# 6_-OPI_POWER.net
KiCad netlist of a schematic drawn in Altium Designer
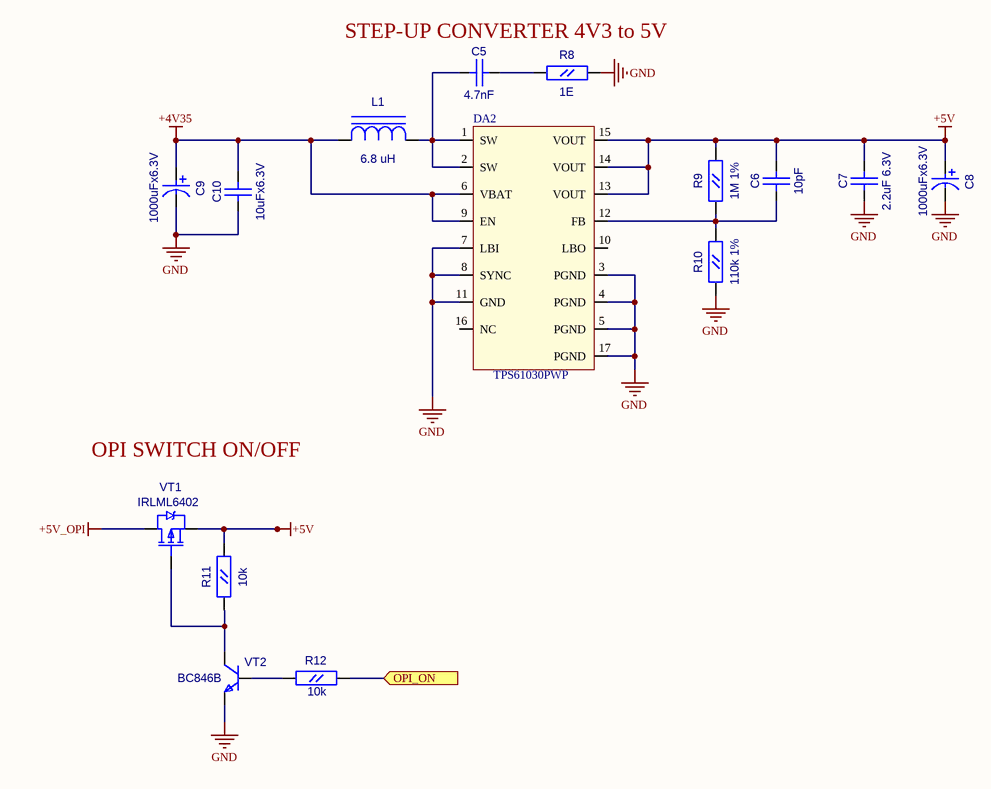
[diagram p0: [6]-OPI_POWER.SchDoc]

(export (version "E")
  (design (tool "Eeschema 10.0.6"))
  (components
    (comp (ref "C5")
      (value "4.7nF")
      (footprint "CC0603")
      (description "CC0603")
      (libsource (lib "gprs_modem_2") (part "CC0603"))
    )
    (comp (ref "C6")
      (value "10pF")
      (footprint "CC0603")
      (description "CC0603")
      (libsource (lib "gprs_modem_2") (part "CC0603"))
    )
    (comp (ref "C7")
      (value "2.2uF 6.3V")
      (footprint "CC0805")
      (description "CC0805")
      (libsource (lib "gprs_modem_2") (part "CC0805"))
    )
    (comp (ref "C8")
      (value "1000uFx6.3V")
      (footprint "CC8X3.5")
      (description "CAP0.35")
      (libsource (lib "gprs_modem_2") (part "CAP0.35"))
    )
    (comp (ref "C9")
      (value "1000uFx6.3V")
      (footprint "CC8X3.5")
      (description "CAP0.35")
      (libsource (lib "gprs_modem_2") (part "CAP0.35"))
    )
    (comp (ref "C10")
      (value "10uFx6.3V")
      (footprint "CC0805")
      (description "CC0805")
      (libsource (lib "gprs_modem_2") (part "CC0805"))
    )
    (comp (ref "DA2")
      (value "TPS61030PWP")
      (footprint "R-PDSO-G16")
      (description "Boost converter")
      (libsource (lib "gprs_modem") (part "TPS61030PWP"))
    )
    (comp (ref "L1")
      (value "6.8 uH")
      (footprint "SDR0805")
      (description "SDR0805")
      (libsource (lib "gprs_modem_2") (part "SDR0805"))
    )
    (comp (ref "R8")
      (value "1E")
      (footprint "RC0603")
      (description "RC0603")
      (libsource (lib "gprs_modem_2") (part "RC0603"))
    )
    (comp (ref "R9")
      (value "1M 1%")
      (footprint "RC0603")
      (description "RC0603")
      (libsource (lib "gprs_modem_2") (part "RC0603"))
    )
    (comp (ref "R10")
      (value "110k 1%")
      (footprint "RC0603")
      (description "RC0603")
      (libsource (lib "gprs_modem_2") (part "RC0603"))
    )
    (comp (ref "R11")
      (value "10k")
      (footprint "RC0603")
      (description "RC0603")
      (libsource (lib "gprs_modem_2") (part "RC0603"))
    )
    (comp (ref "R12")
      (value "10k")
      (footprint "RC0603")
      (description "RC0603")
      (libsource (lib "fizik_lib") (part "RC0603"))
    )
    (comp (ref "VT1")
      (value "IRLML6402")
      (footprint "SOT-23(123)")
      (description "HEXFET Power MOSFET")
      (libsource (lib "gprs_modem_2") (part "IRLML6402"))
    )
    (comp (ref "VT2")
      (value "BC846B")
      (footprint "SOT-23(123)")
      (description "BC846BLT1")
      (libsource (lib "gprs_modem_2") (part "BC846BLT1"))
    )
  )
  (nets
    (net (code "1") (name "+4V35") (class "Default")
      (node (ref "C10") (pin "2") (pinfunction "B_2") (pintype "passive"))
      (node (ref "C9") (pin "1") (pintype "passive"))
      (node (ref "DA2") (pin "6") (pinfunction "VBAT_6") (pintype "passive"))
      (node (ref "DA2") (pin "9") (pinfunction "EN_9") (pintype "passive"))
      (node (ref "L1") (pin "1") (pinfunction "C_1") (pintype "passive"))
    )
    (net (code "2") (name "+5V") (class "Default")
      (node (ref "C6") (pin "2") (pinfunction "B_2") (pintype "passive"))
      (node (ref "C7") (pin "2") (pinfunction "B_2") (pintype "passive"))
      (node (ref "C8") (pin "1") (pintype "passive"))
      (node (ref "DA2") (pin "13") (pinfunction "VOUT_13") (pintype "passive"))
      (node (ref "DA2") (pin "14") (pinfunction "VOUT_14") (pintype "passive"))
      (node (ref "DA2") (pin "15") (pinfunction "VOUT_15") (pintype "passive"))
      (node (ref "R11") (pin "2") (pinfunction "B_2") (pintype "passive"))
      (node (ref "R9") (pin "2") (pinfunction "B_2") (pintype "passive"))
      (node (ref "VT1") (pin "2") (pinfunction "S_2") (pintype "passive"))
    )
    (net (code "3") (name "+5V_OPI") (class "Default")
      (node (ref "VT1") (pin "3") (pinfunction "D_3") (pintype "passive"))
    )
    (net (code "4") (name "/OPI_ON") (class "Default")
      (node (ref "R12") (pin "2") (pinfunction "B_2") (pintype "passive"))
    )
    (net (code "5") (name "GND") (class "Default")
      (node (ref "C10") (pin "1") (pinfunction "A_1") (pintype "passive"))
      (node (ref "C7") (pin "1") (pinfunction "A_1") (pintype "passive"))
      (node (ref "C8") (pin "2") (pintype "passive"))
      (node (ref "C9") (pin "2") (pintype "passive"))
      (node (ref "DA2") (pin "11") (pinfunction "GND_11") (pintype "passive"))
      (node (ref "DA2") (pin "17") (pinfunction "PGND_17") (pintype "passive"))
      (node (ref "DA2") (pin "3") (pinfunction "PGND_3") (pintype "passive"))
      (node (ref "DA2") (pin "4") (pinfunction "PGND_4") (pintype "passive"))
      (node (ref "DA2") (pin "5") (pinfunction "PGND_5") (pintype "passive"))
      (node (ref "DA2") (pin "7") (pinfunction "LBI_7") (pintype "passive"))
      (node (ref "DA2") (pin "8") (pinfunction "SYNC_8") (pintype "passive"))
      (node (ref "R10") (pin "1") (pinfunction "A_1") (pintype "passive"))
      (node (ref "R8") (pin "2") (pinfunction "B_2") (pintype "passive"))
      (node (ref "VT2") (pin "2") (pinfunction "E_2") (pintype "passive"))
    )
    (net (code "6") (name "Net-(C5-A)") (class "Default")
      (node (ref "C5") (pin "1") (pinfunction "A_1") (pintype "passive"))
      (node (ref "DA2") (pin "1") (pinfunction "SW_1") (pintype "passive"))
      (node (ref "DA2") (pin "2") (pinfunction "SW_2") (pintype "passive"))
      (node (ref "L1") (pin "2") (pinfunction "A_2") (pintype "passive"))
    )
    (net (code "7") (name "Net-(C5-B)") (class "Default")
      (node (ref "C5") (pin "2") (pinfunction "B_2") (pintype "passive"))
      (node (ref "R8") (pin "1") (pinfunction "A_1") (pintype "passive"))
    )
    (net (code "8") (name "Net-(C6-A)") (class "Default")
      (node (ref "C6") (pin "1") (pinfunction "A_1") (pintype "passive"))
      (node (ref "DA2") (pin "12") (pinfunction "FB_12") (pintype "passive"))
      (node (ref "R10") (pin "2") (pinfunction "B_2") (pintype "passive"))
      (node (ref "R9") (pin "1") (pinfunction "A_1") (pintype "passive"))
    )
    (net (code "9") (name "Net-(R11-A)") (class "Default")
      (node (ref "R11") (pin "1") (pinfunction "A_1") (pintype "passive"))
      (node (ref "VT1") (pin "1") (pinfunction "G_1") (pintype "passive"))
      (node (ref "VT2") (pin "3") (pinfunction "C_3") (pintype "passive"))
    )
    (net (code "10") (name "Net-(R12-A)") (class "Default")
      (node (ref "R12") (pin "1") (pinfunction "A_1") (pintype "passive"))
      (node (ref "VT2") (pin "1") (pinfunction "B_1") (pintype "passive"))
    )
    (net (code "11") (name "unconnected-(DA2-LBO-Pad10)") (class "Default")
      (node (ref "DA2") (pin "10") (pinfunction "LBO_10") (pintype "passive"))
    )
    (net (code "12") (name "unconnected-(DA2-NC-Pad16)") (class "Default")
      (node (ref "DA2") (pin "16") (pinfunction "NC_16") (pintype "passive"))
    )
  )
)
